# Patch_Anetnna_16_8.net
KiCad netlist of a schematic drawn in EAGLE
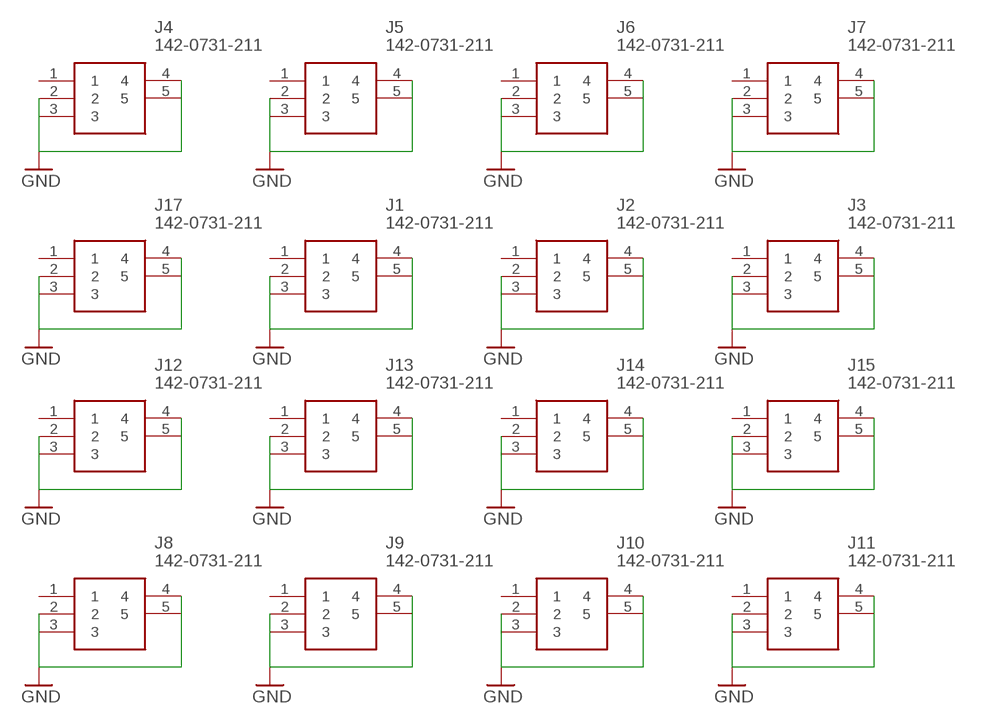
[diagram p0: schematic, sheet 1]

(export (version "E")
  (design (tool "Eeschema 10.0.6"))
  (components
    (comp (ref "J1")
      (value "142-0731-211")
      (footprint "eagle-import:1420731211")
      (fields (field (name "MOUSER_PART_NUMBER") "530-142-0731-211"))
      (libsource (lib "eagle-import") (part "142-0731-211"))
    )
    (comp (ref "J2")
      (value "142-0731-211")
      (footprint "eagle-import:1420731211")
      (fields (field (name "MOUSER_PART_NUMBER") "530-142-0731-211"))
      (libsource (lib "eagle-import") (part "142-0731-211"))
    )
    (comp (ref "J3")
      (value "142-0731-211")
      (footprint "eagle-import:1420731211")
      (fields (field (name "MOUSER_PART_NUMBER") "530-142-0731-211"))
      (libsource (lib "eagle-import") (part "142-0731-211"))
    )
    (comp (ref "J4")
      (value "142-0731-211")
      (footprint "eagle-import:1420731211")
      (fields (field (name "MOUSER_PART_NUMBER") "530-142-0731-211"))
      (libsource (lib "eagle-import") (part "142-0731-211"))
    )
    (comp (ref "J5")
      (value "142-0731-211")
      (footprint "eagle-import:1420731211")
      (fields (field (name "MOUSER_PART_NUMBER") "530-142-0731-211"))
      (libsource (lib "eagle-import") (part "142-0731-211"))
    )
    (comp (ref "J6")
      (value "142-0731-211")
      (footprint "eagle-import:1420731211")
      (fields (field (name "MOUSER_PART_NUMBER") "530-142-0731-211"))
      (libsource (lib "eagle-import") (part "142-0731-211"))
    )
    (comp (ref "J7")
      (value "142-0731-211")
      (footprint "eagle-import:1420731211")
      (fields (field (name "MOUSER_PART_NUMBER") "530-142-0731-211"))
      (libsource (lib "eagle-import") (part "142-0731-211"))
    )
    (comp (ref "J8")
      (value "142-0731-211")
      (footprint "eagle-import:1420731211")
      (fields (field (name "MOUSER_PART_NUMBER") "530-142-0731-211"))
      (libsource (lib "eagle-import") (part "142-0731-211"))
    )
    (comp (ref "J9")
      (value "142-0731-211")
      (footprint "eagle-import:1420731211")
      (fields (field (name "MOUSER_PART_NUMBER") "530-142-0731-211"))
      (libsource (lib "eagle-import") (part "142-0731-211"))
    )
    (comp (ref "J10")
      (value "142-0731-211")
      (footprint "eagle-import:1420731211")
      (fields (field (name "MOUSER_PART_NUMBER") "530-142-0731-211"))
      (libsource (lib "eagle-import") (part "142-0731-211"))
    )
    (comp (ref "J11")
      (value "142-0731-211")
      (footprint "eagle-import:1420731211")
      (fields (field (name "MOUSER_PART_NUMBER") "530-142-0731-211"))
      (libsource (lib "eagle-import") (part "142-0731-211"))
    )
    (comp (ref "J12")
      (value "142-0731-211")
      (footprint "eagle-import:1420731211")
      (fields (field (name "MOUSER_PART_NUMBER") "530-142-0731-211"))
      (libsource (lib "eagle-import") (part "142-0731-211"))
    )
    (comp (ref "J13")
      (value "142-0731-211")
      (footprint "eagle-import:1420731211")
      (fields (field (name "MOUSER_PART_NUMBER") "530-142-0731-211"))
      (libsource (lib "eagle-import") (part "142-0731-211"))
    )
    (comp (ref "J14")
      (value "142-0731-211")
      (footprint "eagle-import:1420731211")
      (fields (field (name "MOUSER_PART_NUMBER") "530-142-0731-211"))
      (libsource (lib "eagle-import") (part "142-0731-211"))
    )
    (comp (ref "J15")
      (value "142-0731-211")
      (footprint "eagle-import:1420731211")
      (fields (field (name "MOUSER_PART_NUMBER") "530-142-0731-211"))
      (libsource (lib "eagle-import") (part "142-0731-211"))
    )
    (comp (ref "J17")
      (value "142-0731-211")
      (footprint "eagle-import:1420731211")
      (fields (field (name "MOUSER_PART_NUMBER") "530-142-0731-211"))
      (libsource (lib "eagle-import") (part "142-0731-211"))
    )
  )
  (nets
    (net (code "1") (name "GND") (class "Default")
      (node (ref "J1") (pin "2") (pinfunction "2_2") (pintype "bidirectional"))
      (node (ref "J1") (pin "3") (pinfunction "3_3") (pintype "bidirectional"))
      (node (ref "J1") (pin "4") (pinfunction "4_4") (pintype "bidirectional"))
      (node (ref "J1") (pin "5") (pinfunction "5_5") (pintype "bidirectional"))
      (node (ref "J10") (pin "2") (pinfunction "2_2") (pintype "bidirectional"))
      (node (ref "J10") (pin "3") (pinfunction "3_3") (pintype "bidirectional"))
      (node (ref "J10") (pin "4") (pinfunction "4_4") (pintype "bidirectional"))
      (node (ref "J10") (pin "5") (pinfunction "5_5") (pintype "bidirectional"))
      (node (ref "J11") (pin "2") (pinfunction "2_2") (pintype "bidirectional"))
      (node (ref "J11") (pin "3") (pinfunction "3_3") (pintype "bidirectional"))
      (node (ref "J11") (pin "4") (pinfunction "4_4") (pintype "bidirectional"))
      (node (ref "J11") (pin "5") (pinfunction "5_5") (pintype "bidirectional"))
      (node (ref "J12") (pin "2") (pinfunction "2_2") (pintype "bidirectional"))
      (node (ref "J12") (pin "3") (pinfunction "3_3") (pintype "bidirectional"))
      (node (ref "J12") (pin "4") (pinfunction "4_4") (pintype "bidirectional"))
      (node (ref "J12") (pin "5") (pinfunction "5_5") (pintype "bidirectional"))
      (node (ref "J13") (pin "2") (pinfunction "2_2") (pintype "bidirectional"))
      (node (ref "J13") (pin "3") (pinfunction "3_3") (pintype "bidirectional"))
      (node (ref "J13") (pin "4") (pinfunction "4_4") (pintype "bidirectional"))
      (node (ref "J13") (pin "5") (pinfunction "5_5") (pintype "bidirectional"))
      (node (ref "J14") (pin "2") (pinfunction "2_2") (pintype "bidirectional"))
      (node (ref "J14") (pin "3") (pinfunction "3_3") (pintype "bidirectional"))
      (node (ref "J14") (pin "4") (pinfunction "4_4") (pintype "bidirectional"))
      (node (ref "J14") (pin "5") (pinfunction "5_5") (pintype "bidirectional"))
      (node (ref "J15") (pin "2") (pinfunction "2_2") (pintype "bidirectional"))
      (node (ref "J15") (pin "3") (pinfunction "3_3") (pintype "bidirectional"))
      (node (ref "J15") (pin "4") (pinfunction "4_4") (pintype "bidirectional"))
      (node (ref "J15") (pin "5") (pinfunction "5_5") (pintype "bidirectional"))
      (node (ref "J17") (pin "2") (pinfunction "2_2") (pintype "bidirectional"))
      (node (ref "J17") (pin "3") (pinfunction "3_3") (pintype "bidirectional"))
      (node (ref "J17") (pin "4") (pinfunction "4_4") (pintype "bidirectional"))
      (node (ref "J17") (pin "5") (pinfunction "5_5") (pintype "bidirectional"))
      (node (ref "J2") (pin "2") (pinfunction "2_2") (pintype "bidirectional"))
      (node (ref "J2") (pin "3") (pinfunction "3_3") (pintype "bidirectional"))
      (node (ref "J2") (pin "4") (pinfunction "4_4") (pintype "bidirectional"))
      (node (ref "J2") (pin "5") (pinfunction "5_5") (pintype "bidirectional"))
      (node (ref "J3") (pin "2") (pinfunction "2_2") (pintype "bidirectional"))
      (node (ref "J3") (pin "3") (pinfunction "3_3") (pintype "bidirectional"))
      (node (ref "J3") (pin "4") (pinfunction "4_4") (pintype "bidirectional"))
      (node (ref "J3") (pin "5") (pinfunction "5_5") (pintype "bidirectional"))
      (node (ref "J4") (pin "2") (pinfunction "2_2") (pintype "bidirectional"))
      (node (ref "J4") (pin "3") (pinfunction "3_3") (pintype "bidirectional"))
      (node (ref "J4") (pin "4") (pinfunction "4_4") (pintype "bidirectional"))
      (node (ref "J4") (pin "5") (pinfunction "5_5") (pintype "bidirectional"))
      (node (ref "J5") (pin "2") (pinfunction "2_2") (pintype "bidirectional"))
      (node (ref "J5") (pin "3") (pinfunction "3_3") (pintype "bidirectional"))
      (node (ref "J5") (pin "4") (pinfunction "4_4") (pintype "bidirectional"))
      (node (ref "J5") (pin "5") (pinfunction "5_5") (pintype "bidirectional"))
      (node (ref "J6") (pin "2") (pinfunction "2_2") (pintype "bidirectional"))
      (node (ref "J6") (pin "3") (pinfunction "3_3") (pintype "bidirectional"))
      (node (ref "J6") (pin "4") (pinfunction "4_4") (pintype "bidirectional"))
      (node (ref "J6") (pin "5") (pinfunction "5_5") (pintype "bidirectional"))
      (node (ref "J7") (pin "2") (pinfunction "2_2") (pintype "bidirectional"))
      (node (ref "J7") (pin "3") (pinfunction "3_3") (pintype "bidirectional"))
      (node (ref "J7") (pin "4") (pinfunction "4_4") (pintype "bidirectional"))
      (node (ref "J7") (pin "5") (pinfunction "5_5") (pintype "bidirectional"))
      (node (ref "J8") (pin "2") (pinfunction "2_2") (pintype "bidirectional"))
      (node (ref "J8") (pin "3") (pinfunction "3_3") (pintype "bidirectional"))
      (node (ref "J8") (pin "4") (pinfunction "4_4") (pintype "bidirectional"))
      (node (ref "J8") (pin "5") (pinfunction "5_5") (pintype "bidirectional"))
      (node (ref "J9") (pin "2") (pinfunction "2_2") (pintype "bidirectional"))
      (node (ref "J9") (pin "3") (pinfunction "3_3") (pintype "bidirectional"))
      (node (ref "J9") (pin "4") (pinfunction "4_4") (pintype "bidirectional"))
      (node (ref "J9") (pin "5") (pinfunction "5_5") (pintype "bidirectional"))
    )
    (net (code "2") (name "unconnected-(J1-Pad1)") (class "Default")
      (node (ref "J1") (pin "1") (pinfunction "1_1") (pintype "bidirectional"))
    )
    (net (code "3") (name "unconnected-(J2-Pad1)") (class "Default")
      (node (ref "J2") (pin "1") (pinfunction "1_1") (pintype "bidirectional"))
    )
    (net (code "4") (name "unconnected-(J3-Pad1)") (class "Default")
      (node (ref "J3") (pin "1") (pinfunction "1_1") (pintype "bidirectional"))
    )
    (net (code "5") (name "unconnected-(J4-Pad1)") (class "Default")
      (node (ref "J4") (pin "1") (pinfunction "1_1") (pintype "bidirectional"))
    )
    (net (code "6") (name "unconnected-(J5-Pad1)") (class "Default")
      (node (ref "J5") (pin "1") (pinfunction "1_1") (pintype "bidirectional"))
    )
    (net (code "7") (name "unconnected-(J6-Pad1)") (class "Default")
      (node (ref "J6") (pin "1") (pinfunction "1_1") (pintype "bidirectional"))
    )
    (net (code "8") (name "unconnected-(J7-Pad1)") (class "Default")
      (node (ref "J7") (pin "1") (pinfunction "1_1") (pintype "bidirectional"))
    )
    (net (code "9") (name "unconnected-(J8-Pad1)") (class "Default")
      (node (ref "J8") (pin "1") (pinfunction "1_1") (pintype "bidirectional"))
    )
    (net (code "10") (name "unconnected-(J9-Pad1)") (class "Default")
      (node (ref "J9") (pin "1") (pinfunction "1_1") (pintype "bidirectional"))
    )
    (net (code "11") (name "unconnected-(J10-Pad1)") (class "Default")
      (node (ref "J10") (pin "1") (pinfunction "1_1") (pintype "bidirectional"))
    )
    (net (code "12") (name "unconnected-(J11-Pad1)") (class "Default")
      (node (ref "J11") (pin "1") (pinfunction "1_1") (pintype "bidirectional"))
    )
    (net (code "13") (name "unconnected-(J12-Pad1)") (class "Default")
      (node (ref "J12") (pin "1") (pinfunction "1_1") (pintype "bidirectional"))
    )
    (net (code "14") (name "unconnected-(J13-Pad1)") (class "Default")
      (node (ref "J13") (pin "1") (pinfunction "1_1") (pintype "bidirectional"))
    )
    (net (code "15") (name "unconnected-(J14-Pad1)") (class "Default")
      (node (ref "J14") (pin "1") (pinfunction "1_1") (pintype "bidirectional"))
    )
    (net (code "16") (name "unconnected-(J15-Pad1)") (class "Default")
      (node (ref "J15") (pin "1") (pinfunction "1_1") (pintype "bidirectional"))
    )
    (net (code "17") (name "unconnected-(J17-Pad1)") (class "Default")
      (node (ref "J17") (pin "1") (pinfunction "1_1") (pintype "bidirectional"))
    )
  )
)
